# USB.net
KiCad netlist of a schematic drawn in Altium Designer
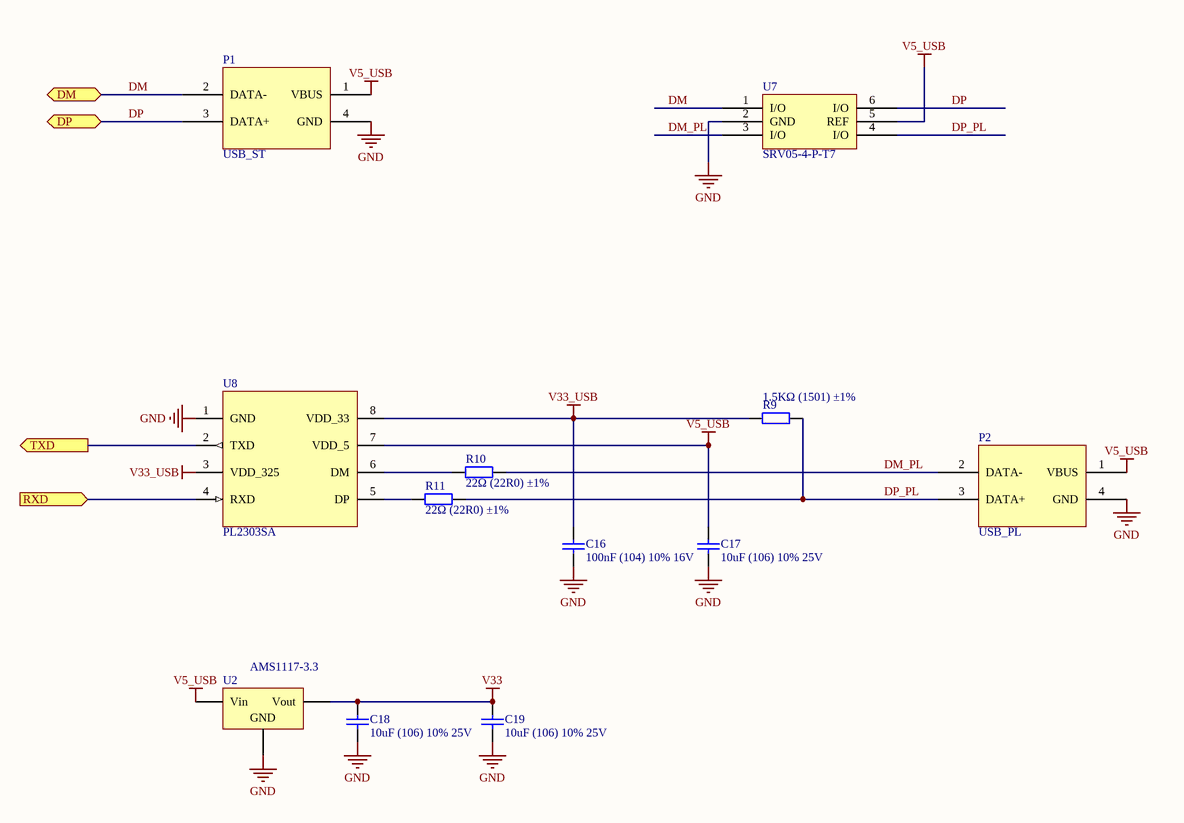
[diagram p0: USB.SchDoc]

(export (version "E")
  (design (tool "Eeschema 10.0.6"))
  (components
    (comp (ref "C16")
      (value "100nF (104) 10% 16V")
      (footprint "0402_C")
      (description "贴片电容")
      (libsource (lib "Miscellaneous Devices LC") (part "0402 100nF (104) 10% 16V"))
    )
    (comp (ref "C17")
      (value "10uF (106) 10% 25V")
      (footprint "0805_C")
      (description "贴片电容")
      (libsource (lib "Miscellaneous Devices LC") (part "0805 10uF (106) 10% 25V"))
    )
    (comp (ref "C18")
      (value "10uF (106) 10% 25V")
      (footprint "0805_C")
      (description "贴片电容")
      (libsource (lib "Miscellaneous Devices LC") (part "0805 10uF (106) 10% 25V"))
    )
    (comp (ref "C19")
      (value "10uF (106) 10% 25V")
      (footprint "0805_C")
      (description "贴片电容")
      (libsource (lib "Miscellaneous Devices LC") (part "0805 10uF (106) 10% 25V"))
    )
    (comp (ref "P1")
      (value "USB_ST")
      (footprint "USB-B/Female")
      (description "USB-B/Female")
      (libsource (lib "Temp") (part "USB-B/Female"))
    )
    (comp (ref "P2")
      (value "USB_PL")
      (footprint "USB-B/Female")
      (description "USB-B/Female")
      (libsource (lib "Temp") (part "USB-B/Female"))
    )
    (comp (ref "R9")
      (value "1.5KΩ (1501) ±1%")
      (footprint "0402_R")
      (description "贴片电阻")
      (libsource (lib "Miscellaneous Devices LC") (part "0402 1.5KΩ (1501) 1%"))
    )
    (comp (ref "R10")
      (value "22Ω (22R0) ±1%")
      (footprint "0402_R")
      (description "贴片电阻")
      (libsource (lib "Miscellaneous Devices LC") (part "0402 22Ω (22R0) 1%"))
    )
    (comp (ref "R11")
      (value "22Ω (22R0) ±1%")
      (footprint "0402_R")
      (description "贴片电阻")
      (libsource (lib "Miscellaneous Devices LC") (part "0402 22Ω (22R0) 1%"))
    )
    (comp (ref "U2")
      (value "AMS1117-3.3")
      (footprint "SOT-223")
      (description "低压差线性稳压(LDO)")
      (libsource (lib "Miscellaneous Devices LC") (part "SOT-223 AMS1117-3.3"))
    )
    (comp (ref "U7")
      (value "SRV05-4-P-T7")
      (footprint "SOT-23-6")
      (description "TVS")
      (libsource (lib "Miscellaneous Devices LC") (part "SRV05-4-P-T7_[C85364]"))
    )
    (comp (ref "U8") (value "PL2303SA") (footprint "SOP-8_150mil") (libsource (lib "Temp") (part "PL2303SA")))
  )
  (nets
    (net (code "1") (name "/DM") (class "Default")
      (node (ref "P1") (pin "2") (pinfunction "DATA-_2") (pintype "passive"))
      (node (ref "U7") (pin "1") (pinfunction "I/O_1") (pintype "passive"))
    )
    (net (code "2") (name "/DM_PL") (class "Default")
      (node (ref "P2") (pin "2") (pinfunction "DATA-_2") (pintype "passive"))
      (node (ref "R10") (pin "2") (pinfunction "2_2") (pintype "passive"))
      (node (ref "U7") (pin "3") (pinfunction "I/O_3") (pintype "passive"))
    )
    (net (code "3") (name "/DP") (class "Default")
      (node (ref "P1") (pin "3") (pinfunction "DATA+_3") (pintype "passive"))
      (node (ref "U7") (pin "6") (pinfunction "I/O_6") (pintype "passive"))
    )
    (net (code "4") (name "/DP_PL") (class "Default")
      (node (ref "P2") (pin "3") (pinfunction "DATA+_3") (pintype "passive"))
      (node (ref "R11") (pin "2") (pinfunction "2_2") (pintype "passive"))
      (node (ref "R9") (pin "1") (pinfunction "1_1") (pintype "passive"))
      (node (ref "U7") (pin "4") (pinfunction "I/O_4") (pintype "passive"))
    )
    (net (code "5") (name "/RXD") (class "Default")
      (node (ref "U8") (pin "4") (pinfunction "RXD_4") (pintype "input"))
    )
    (net (code "6") (name "/TXD") (class "Default")
      (node (ref "U8") (pin "2") (pinfunction "TXD_2") (pintype "output"))
    )
    (net (code "7") (name "GND") (class "Default")
      (node (ref "C16") (pin "1") (pinfunction "1_1") (pintype "passive"))
      (node (ref "C17") (pin "1") (pinfunction "1_1") (pintype "passive"))
      (node (ref "C18") (pin "1") (pinfunction "1_1") (pintype "passive"))
      (node (ref "C19") (pin "1") (pinfunction "1_1") (pintype "passive"))
      (node (ref "P1") (pin "4") (pinfunction "GND_4") (pintype "passive"))
      (node (ref "P2") (pin "4") (pinfunction "GND_4") (pintype "passive"))
      (node (ref "U2") (pin "1") (pinfunction "GND_1") (pintype "passive"))
      (node (ref "U7") (pin "2") (pinfunction "GND_2") (pintype "passive"))
      (node (ref "U8") (pin "1") (pinfunction "GND_1") (pintype "power_in"))
    )
    (net (code "8") (name "Net-(U8-DM)") (class "Default")
      (node (ref "R10") (pin "1") (pinfunction "1_1") (pintype "passive"))
      (node (ref "U8") (pin "6") (pinfunction "DM_6") (pintype "passive"))
    )
    (net (code "9") (name "Net-(U8-DP)") (class "Default")
      (node (ref "R11") (pin "1") (pinfunction "1_1") (pintype "passive"))
      (node (ref "U8") (pin "5") (pinfunction "DP_5") (pintype "passive"))
    )
    (net (code "10") (name "V5_USB") (class "Default")
      (node (ref "C17") (pin "2") (pinfunction "2_2") (pintype "passive"))
      (node (ref "P1") (pin "1") (pinfunction "VBUS_1") (pintype "passive"))
      (node (ref "P2") (pin "1") (pinfunction "VBUS_1") (pintype "passive"))
      (node (ref "U2") (pin "3") (pinfunction "Vin_3") (pintype "passive"))
      (node (ref "U7") (pin "5") (pinfunction "REF_5") (pintype "passive"))
      (node (ref "U8") (pin "7") (pinfunction "VDD_5_7") (pintype "power_in"))
    )
    (net (code "11") (name "V33") (class "Default")
      (node (ref "C18") (pin "2") (pinfunction "2_2") (pintype "passive"))
      (node (ref "C19") (pin "2") (pinfunction "2_2") (pintype "passive"))
      (node (ref "U2") (pin "2") (pinfunction "Vout_2") (pintype "passive"))
    )
    (net (code "12") (name "V33_USB") (class "Default")
      (node (ref "C16") (pin "2") (pinfunction "2_2") (pintype "passive"))
      (node (ref "R9") (pin "2") (pinfunction "2_2") (pintype "passive"))
      (node (ref "U8") (pin "3") (pinfunction "VDD_325_3") (pintype "power_in"))
      (node (ref "U8") (pin "8") (pinfunction "VDD_33_8") (pintype "power_in"))
    )
  )
)
